# Microcontroller_STM32F101.net
KiCad netlist of a schematic drawn in Altium Designer
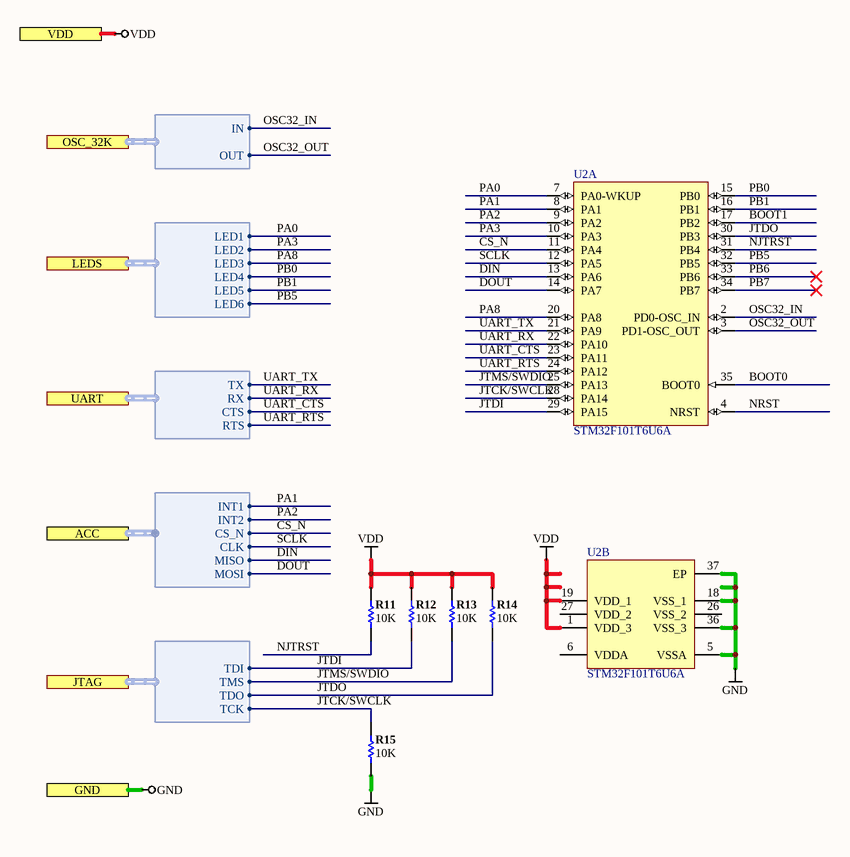
[diagram p0: Microcontroller_STM32F101.SchDoc]

(export (version "E")
  (design (tool "Eeschema 10.0.6"))
  (components
    (comp (ref "R11")
      (value "10K")
      (footprint "RESC0402(1005)_N")
      (description "10K 0.063W 5% 0402 (1005 Metric)  SMD")
      (fields (field (name "TOLERANCE") "5 %") (field (name "POWER") "0.063 W"))
      (libsource (lib "Altium Content Vault") (part "CMP-1011-00098-1"))
    )
    (comp (ref "R12")
      (value "10K")
      (footprint "RESC0402(1005)_N")
      (description "10K 0.063W 5% 0402 (1005 Metric)  SMD")
      (fields (field (name "TOLERANCE") "5 %") (field (name "POWER") "0.063 W"))
      (libsource (lib "Altium Content Vault") (part "CMP-1011-00098-1"))
    )
    (comp (ref "R13")
      (value "10K")
      (footprint "RESC0402(1005)_N")
      (description "10K 0.063W 5% 0402 (1005 Metric)  SMD")
      (fields (field (name "TOLERANCE") "5 %") (field (name "POWER") "0.063 W"))
      (libsource (lib "Altium Content Vault") (part "CMP-1011-00098-1"))
    )
    (comp (ref "R14")
      (value "10K")
      (footprint "RESC0402(1005)_N")
      (description "10K 0.063W 5% 0402 (1005 Metric)  SMD")
      (fields (field (name "TOLERANCE") "5 %") (field (name "POWER") "0.063 W"))
      (libsource (lib "Altium Content Vault") (part "CMP-1011-00098-1"))
    )
    (comp (ref "R15")
      (value "10K")
      (footprint "RESC0402(1005)_N")
      (description "10K 0.063W 5% 0402 (1005 Metric)  SMD")
      (fields (field (name "TOLERANCE") "5 %") (field (name "POWER") "0.063 W"))
      (libsource (lib "Altium Content Vault") (part "CMP-1011-00098-1"))
    )
    (comp (ref "U2")
      (value "STM32F101T6U6A")
      (footprint "STM-VFQFPN36_N")
      (libsource (lib "Altium Content Vault") (part "MC-ARM-STM32F101X4_6-SQ37"))
    )
  )
  (nets
    (net (code "6") (name "/BOOT0") (class "Default")
      (node (ref "U2") (pin "35") (pinfunction "BOOT0_35") (pintype "input"))
    )
    (net (code "7") (name "/BOOT1") (class "Default")
      (node (ref "U2") (pin "17") (pinfunction "PB2_17") (pintype "bidirectional"))
    )
    (net (code "8") (name "/CS_N") (class "Default")
      (node (ref "U2") (pin "11") (pinfunction "PA4_11") (pintype "bidirectional"))
    )
    (net (code "9") (name "/DIN") (class "Default")
      (node (ref "U2") (pin "13") (pinfunction "PA6_13") (pintype "bidirectional"))
    )
    (net (code "10") (name "/DOUT") (class "Default")
      (node (ref "U2") (pin "14") (pinfunction "PA7_14") (pintype "bidirectional"))
    )
    (net (code "11") (name "/JTCK{slash}SWCLK") (class "Default")
      (node (ref "R15") (pin "2") (pinfunction "2_2") (pintype "passive"))
      (node (ref "U2") (pin "28") (pinfunction "PA14_28") (pintype "bidirectional"))
    )
    (net (code "12") (name "/JTDI") (class "Default")
      (node (ref "R12") (pin "1") (pinfunction "1_1") (pintype "passive"))
      (node (ref "U2") (pin "29") (pinfunction "PA15_29") (pintype "bidirectional"))
    )
    (net (code "13") (name "/JTDO") (class "Default")
      (node (ref "R14") (pin "1") (pinfunction "1_1") (pintype "passive"))
      (node (ref "U2") (pin "30") (pinfunction "PB3_30") (pintype "bidirectional"))
    )
    (net (code "14") (name "/JTMS{slash}SWDIO") (class "Default")
      (node (ref "R13") (pin "1") (pinfunction "1_1") (pintype "passive"))
      (node (ref "U2") (pin "25") (pinfunction "PA13_25") (pintype "bidirectional"))
    )
    (net (code "15") (name "/NJTRST") (class "Default")
      (node (ref "R11") (pin "1") (pinfunction "1_1") (pintype "passive"))
      (node (ref "U2") (pin "31") (pinfunction "PB4_31") (pintype "bidirectional"))
    )
    (net (code "16") (name "/NRST") (class "Default")
      (node (ref "U2") (pin "4") (pinfunction "NRST_4") (pintype "bidirectional"))
    )
    (net (code "17") (name "/OSC32_IN") (class "Default")
      (node (ref "U2") (pin "2") (pinfunction "PD0-OSC_IN_2") (pintype "bidirectional"))
    )
    (net (code "18") (name "/OSC32_OUT") (class "Default")
      (node (ref "U2") (pin "3") (pinfunction "PD1-OSC_OUT_3") (pintype "bidirectional"))
    )
    (net (code "19") (name "/PA0") (class "Default")
      (node (ref "U2") (pin "7") (pinfunction "PA0-WKUP_7") (pintype "bidirectional"))
    )
    (net (code "20") (name "/PA1") (class "Default")
      (node (ref "U2") (pin "8") (pinfunction "PA1_8") (pintype "bidirectional"))
    )
    (net (code "21") (name "/PA2") (class "Default")
      (node (ref "U2") (pin "9") (pinfunction "PA2_9") (pintype "bidirectional"))
    )
    (net (code "22") (name "/PA3") (class "Default")
      (node (ref "U2") (pin "10") (pinfunction "PA3_10") (pintype "bidirectional"))
    )
    (net (code "23") (name "/PA8") (class "Default")
      (node (ref "U2") (pin "20") (pinfunction "PA8_20") (pintype "bidirectional"))
    )
    (net (code "24") (name "/PB0") (class "Default")
      (node (ref "U2") (pin "15") (pinfunction "PB0_15") (pintype "bidirectional"))
    )
    (net (code "25") (name "/PB1") (class "Default")
      (node (ref "U2") (pin "16") (pinfunction "PB1_16") (pintype "bidirectional"))
    )
    (net (code "26") (name "/PB5") (class "Default")
      (node (ref "U2") (pin "32") (pinfunction "PB5_32") (pintype "bidirectional"))
    )
    (net (code "27") (name "/PB6") (class "Default")
      (node (ref "U2") (pin "33") (pinfunction "PB6_33") (pintype "bidirectional+no_connect"))
    )
    (net (code "28") (name "/PB7") (class "Default")
      (node (ref "U2") (pin "34") (pinfunction "PB7_34") (pintype "bidirectional+no_connect"))
    )
    (net (code "29") (name "/SCLK") (class "Default")
      (node (ref "U2") (pin "12") (pinfunction "PA5_12") (pintype "bidirectional"))
    )
    (net (code "30") (name "/UART_CTS") (class "Default")
      (node (ref "U2") (pin "23") (pinfunction "PA11_23") (pintype "bidirectional"))
    )
    (net (code "31") (name "/UART_RTS") (class "Default")
      (node (ref "U2") (pin "24") (pinfunction "PA12_24") (pintype "bidirectional"))
    )
    (net (code "32") (name "/UART_RX") (class "Default")
      (node (ref "U2") (pin "22") (pinfunction "PA10_22") (pintype "bidirectional"))
    )
    (net (code "33") (name "/UART_TX") (class "Default")
      (node (ref "U2") (pin "21") (pinfunction "PA9_21") (pintype "bidirectional"))
    )
    (net (code "39") (name "GND") (class "Default")
      (node (ref "R15") (pin "1") (pinfunction "1_1") (pintype "passive"))
      (node (ref "U2") (pin "18") (pinfunction "VSS_1_18") (pintype "power_in"))
      (node (ref "U2") (pin "36") (pinfunction "VSS_3_36") (pintype "power_in"))
      (node (ref "U2") (pin "37") (pinfunction "EP_37") (pintype "power_in"))
      (node (ref "U2") (pin "5") (pinfunction "VSSA_5") (pintype "power_in"))
    )
    (net (code "40") (name "VDD") (class "Default")
      (node (ref "R11") (pin "2") (pinfunction "2_2") (pintype "passive"))
      (node (ref "R12") (pin "2") (pinfunction "2_2") (pintype "passive"))
      (node (ref "R13") (pin "2") (pinfunction "2_2") (pintype "passive"))
      (node (ref "R14") (pin "2") (pinfunction "2_2") (pintype "passive"))
      (node (ref "U2") (pin "1") (pinfunction "VDD_3_1") (pintype "power_in"))
      (node (ref "U2") (pin "19") (pinfunction "VDD_1_19") (pintype "power_in"))
    )
    (net (code "41") (name "unconnected-(U2B-VDDA-Pad6)") (class "Default")
      (node (ref "U2") (pin "6") (pinfunction "VDDA_6") (pintype "power_in"))
    )
    (net (code "42") (name "unconnected-(U2B-VDD_2-Pad27)") (class "Default")
      (node (ref "U2") (pin "27") (pinfunction "VDD_2_27") (pintype "power_in"))
    )
    (net (code "43") (name "unconnected-(U2B-VSS_2-Pad26)") (class "Default")
      (node (ref "U2") (pin "26") (pinfunction "VSS_2_26") (pintype "power_in"))
    )
  )
)
